# Connection_board.net
KiCad netlist of a schematic drawn in EAGLE
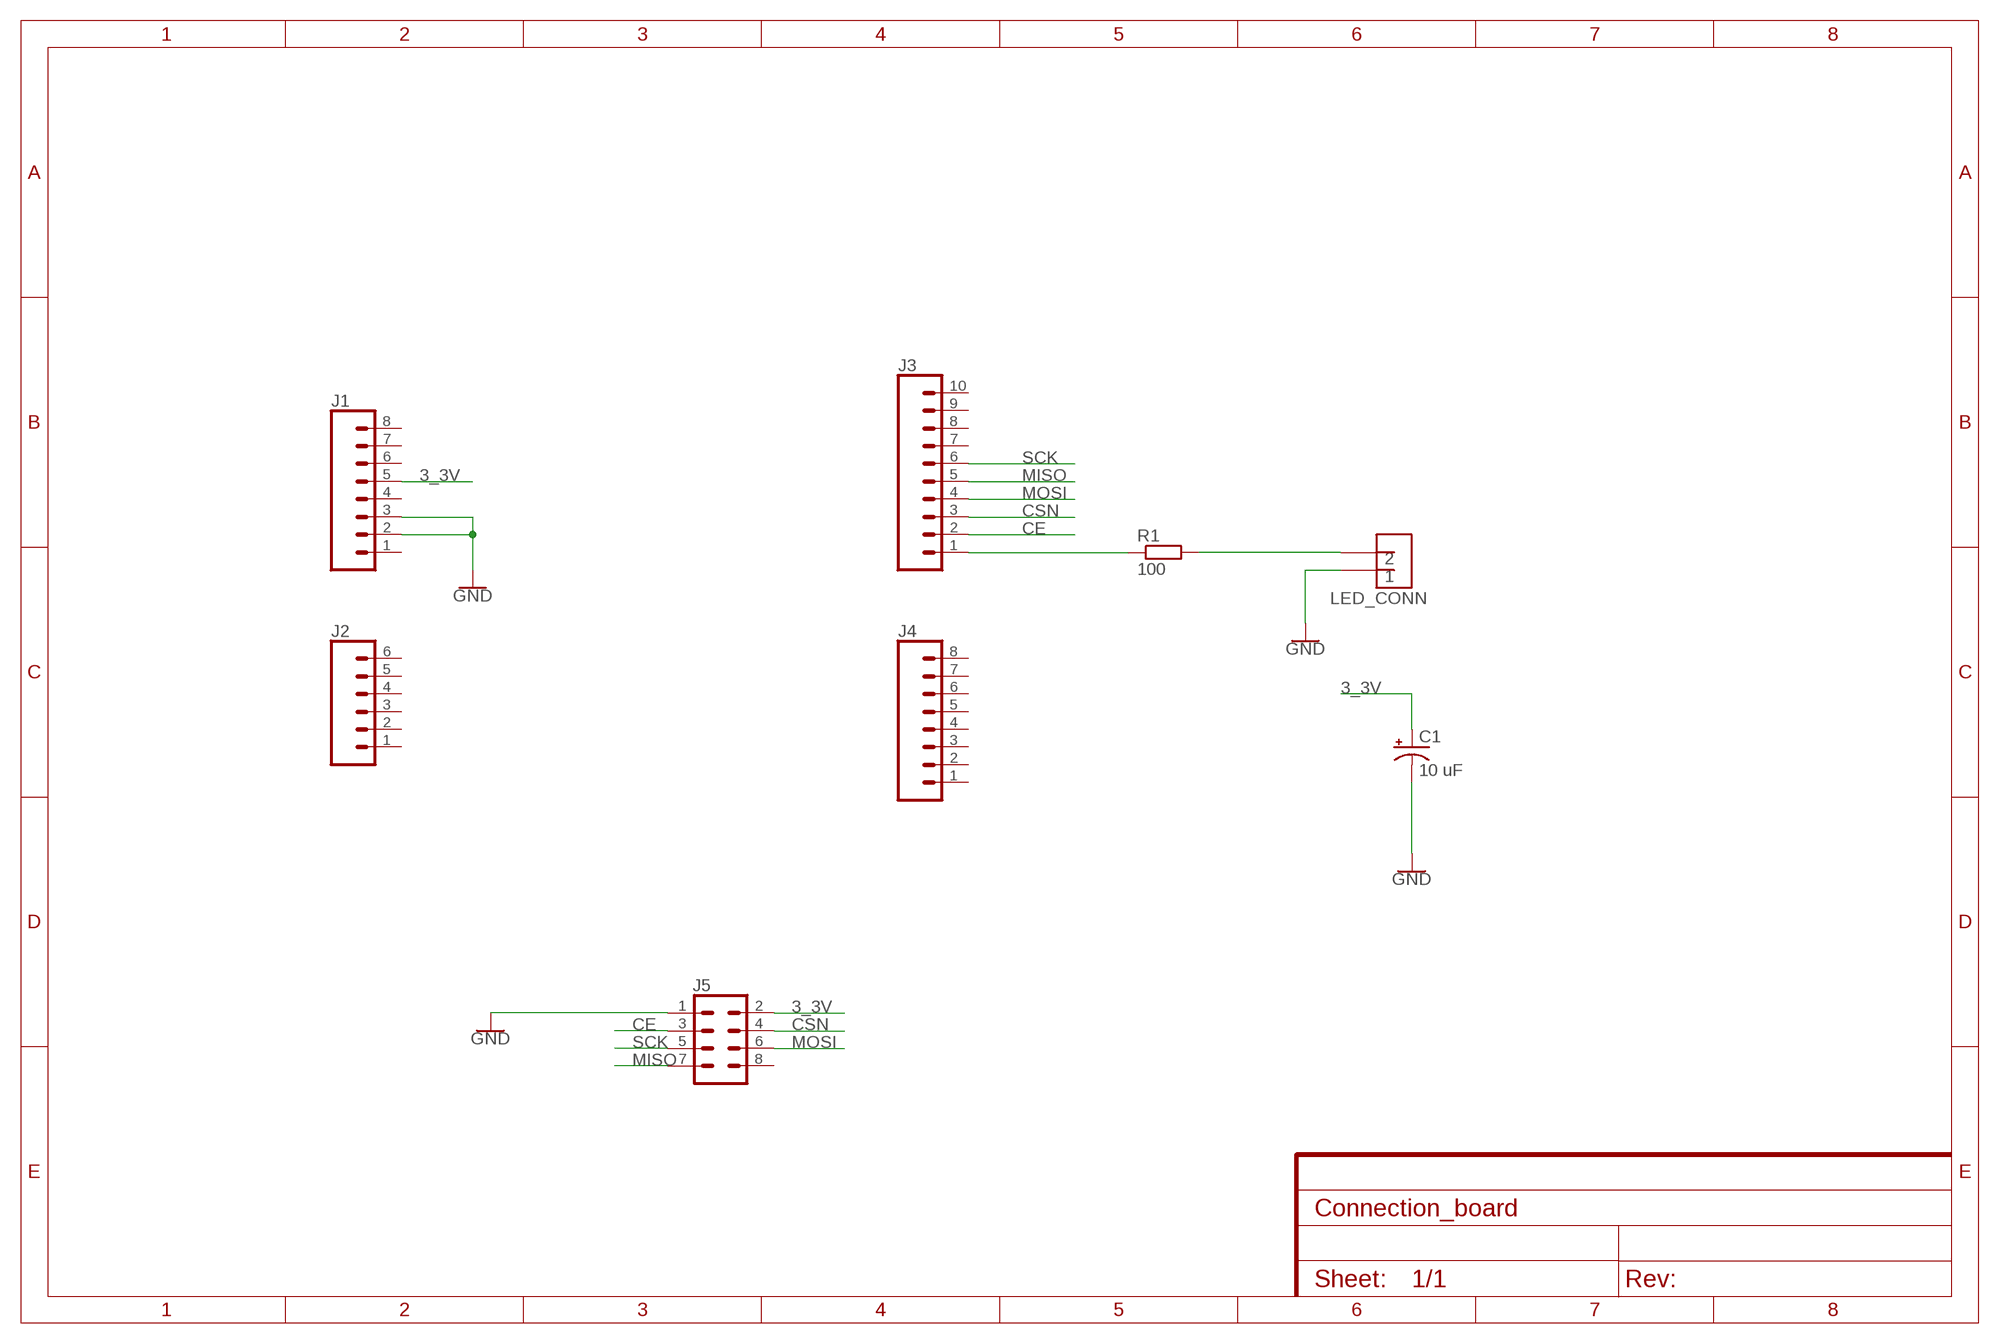
[diagram p0: schematic, sheet 1]

(export (version "E")
  (design (tool "Eeschema 10.0.6"))
  (components
    (comp (ref "C1")
      (value "10 uF")
      (footprint "eagle-import:E2-5")
      (libsource (lib "eagle-import") (part "CPOL-USE2-5"))
    )
    (comp (ref "J1")
      (value "CONN_08\"")
      (footprint "eagle-import:1X08")
      (libsource (lib "eagle-import") (part "CONN_08{dblquote}"))
    )
    (comp (ref "J2")
      (value "CONN_06SILK_FEMALE_PTH")
      (footprint "eagle-import:1X06")
      (libsource (lib "eagle-import") (part "CONN_06SILK_FEMALE_PTH"))
    )
    (comp (ref "J3")
      (value "CONN_10\"")
      (footprint "eagle-import:1X10")
      (libsource (lib "eagle-import") (part "CONN_10{dblquote}"))
    )
    (comp (ref "J4")
      (value "CONN_08\"")
      (footprint "eagle-import:1X08")
      (libsource (lib "eagle-import") (part "CONN_08{dblquote}"))
    )
    (comp (ref "J5")
      (value "CONN_04X2")
      (footprint "eagle-import:2X4")
      (libsource (lib "eagle-import") (part "CONN_04X2"))
    )
    (comp (ref "LED_CONN")
      (value "JST_2")
      (footprint "eagle-import:JST_2")
      (libsource (lib "eagle-import") (part "JST_2"))
    )
    (comp (ref "R1")
      (value "100")
      (footprint "eagle-import:0207_10")
      (libsource (lib "eagle-import") (part "R-EU_0207/10"))
    )
  )
  (nets
    (net (code "1") (name "/3_3V") (class "Default")
      (node (ref "C1") (pin "+") (pinfunction "+_+") (pintype "passive"))
      (node (ref "J1") (pin "5") (pinfunction "5_5") (pintype "passive"))
      (node (ref "J5") (pin "2") (pinfunction "2_2") (pintype "passive"))
    )
    (net (code "2") (name "/CE") (class "Default")
      (node (ref "J3") (pin "2") (pinfunction "2_2") (pintype "passive"))
      (node (ref "J5") (pin "3") (pinfunction "3_3") (pintype "passive"))
    )
    (net (code "3") (name "/CSN") (class "Default")
      (node (ref "J3") (pin "3") (pinfunction "3_3") (pintype "passive"))
      (node (ref "J5") (pin "4") (pinfunction "4_4") (pintype "passive"))
    )
    (net (code "4") (name "/MISO") (class "Default")
      (node (ref "J3") (pin "5") (pinfunction "5_5") (pintype "passive"))
      (node (ref "J5") (pin "7") (pinfunction "7_7") (pintype "passive"))
    )
    (net (code "5") (name "/MOSI") (class "Default")
      (node (ref "J3") (pin "4") (pinfunction "4_4") (pintype "passive"))
      (node (ref "J5") (pin "6") (pinfunction "6_6") (pintype "passive"))
    )
    (net (code "6") (name "/SCK") (class "Default")
      (node (ref "J3") (pin "6") (pinfunction "6_6") (pintype "passive"))
      (node (ref "J5") (pin "5") (pinfunction "5_5") (pintype "passive"))
    )
    (net (code "7") (name "GND") (class "Default")
      (node (ref "C1") (pin "-") (pinfunction "-_-") (pintype "passive"))
      (node (ref "J1") (pin "2") (pinfunction "2_2") (pintype "passive"))
      (node (ref "J1") (pin "3") (pinfunction "3_3") (pintype "passive"))
      (node (ref "J5") (pin "1") (pinfunction "1_1") (pintype "passive"))
      (node (ref "LED_CONN") (pin "P$1") (pinfunction "P$1_P$1") (pintype "bidirectional"))
    )
    (net (code "8") (name "Net-(J3-Pad1)") (class "Default")
      (node (ref "J3") (pin "1") (pinfunction "1_1") (pintype "passive"))
      (node (ref "R1") (pin "1") (pinfunction "1_1") (pintype "passive"))
    )
    (net (code "9") (name "Net-(LED_CONN-PadP$2)") (class "Default")
      (node (ref "LED_CONN") (pin "P$2") (pinfunction "P$2_P$2") (pintype "bidirectional"))
      (node (ref "R1") (pin "2") (pinfunction "2_2") (pintype "passive"))
    )
    (net (code "10") (name "unconnected-(J1-Pad1)") (class "Default")
      (node (ref "J1") (pin "1") (pinfunction "1_1") (pintype "passive"))
    )
    (net (code "11") (name "unconnected-(J1-Pad4)") (class "Default")
      (node (ref "J1") (pin "4") (pinfunction "4_4") (pintype "passive"))
    )
    (net (code "12") (name "unconnected-(J1-Pad6)") (class "Default")
      (node (ref "J1") (pin "6") (pinfunction "6_6") (pintype "passive"))
    )
    (net (code "13") (name "unconnected-(J1-Pad7)") (class "Default")
      (node (ref "J1") (pin "7") (pinfunction "7_7") (pintype "passive"))
    )
    (net (code "14") (name "unconnected-(J1-Pad8)") (class "Default")
      (node (ref "J1") (pin "8") (pinfunction "8_8") (pintype "passive"))
    )
    (net (code "15") (name "unconnected-(J2-Pad1)") (class "Default")
      (node (ref "J2") (pin "1") (pinfunction "1_1") (pintype "passive"))
    )
    (net (code "16") (name "unconnected-(J2-Pad2)") (class "Default")
      (node (ref "J2") (pin "2") (pinfunction "2_2") (pintype "passive"))
    )
    (net (code "17") (name "unconnected-(J2-Pad3)") (class "Default")
      (node (ref "J2") (pin "3") (pinfunction "3_3") (pintype "passive"))
    )
    (net (code "18") (name "unconnected-(J2-Pad4)") (class "Default")
      (node (ref "J2") (pin "4") (pinfunction "4_4") (pintype "passive"))
    )
    (net (code "19") (name "unconnected-(J2-Pad5)") (class "Default")
      (node (ref "J2") (pin "5") (pinfunction "5_5") (pintype "passive"))
    )
    (net (code "20") (name "unconnected-(J2-Pad6)") (class "Default")
      (node (ref "J2") (pin "6") (pinfunction "6_6") (pintype "passive"))
    )
    (net (code "21") (name "unconnected-(J3-Pad7)") (class "Default")
      (node (ref "J3") (pin "7") (pinfunction "7_7") (pintype "passive"))
    )
    (net (code "22") (name "unconnected-(J3-Pad8)") (class "Default")
      (node (ref "J3") (pin "8") (pinfunction "8_8") (pintype "passive"))
    )
    (net (code "23") (name "unconnected-(J3-Pad9)") (class "Default")
      (node (ref "J3") (pin "9") (pinfunction "9_9") (pintype "passive"))
    )
    (net (code "24") (name "unconnected-(J3-Pad10)") (class "Default")
      (node (ref "J3") (pin "10") (pinfunction "10_10") (pintype "passive"))
    )
    (net (code "25") (name "unconnected-(J4-Pad1)") (class "Default")
      (node (ref "J4") (pin "1") (pinfunction "1_1") (pintype "passive"))
    )
    (net (code "26") (name "unconnected-(J4-Pad2)") (class "Default")
      (node (ref "J4") (pin "2") (pinfunction "2_2") (pintype "passive"))
    )
    (net (code "27") (name "unconnected-(J4-Pad3)") (class "Default")
      (node (ref "J4") (pin "3") (pinfunction "3_3") (pintype "passive"))
    )
    (net (code "28") (name "unconnected-(J4-Pad4)") (class "Default")
      (node (ref "J4") (pin "4") (pinfunction "4_4") (pintype "passive"))
    )
    (net (code "29") (name "unconnected-(J4-Pad5)") (class "Default")
      (node (ref "J4") (pin "5") (pinfunction "5_5") (pintype "passive"))
    )
    (net (code "30") (name "unconnected-(J4-Pad6)") (class "Default")
      (node (ref "J4") (pin "6") (pinfunction "6_6") (pintype "passive"))
    )
    (net (code "31") (name "unconnected-(J4-Pad7)") (class "Default")
      (node (ref "J4") (pin "7") (pinfunction "7_7") (pintype "passive"))
    )
    (net (code "32") (name "unconnected-(J4-Pad8)") (class "Default")
      (node (ref "J4") (pin "8") (pinfunction "8_8") (pintype "passive"))
    )
    (net (code "33") (name "unconnected-(J5-Pad8)") (class "Default")
      (node (ref "J5") (pin "8") (pinfunction "8_8") (pintype "passive"))
    )
  )
)
